# SineGenerator.net
KiCad netlist of a schematic drawn in EAGLE
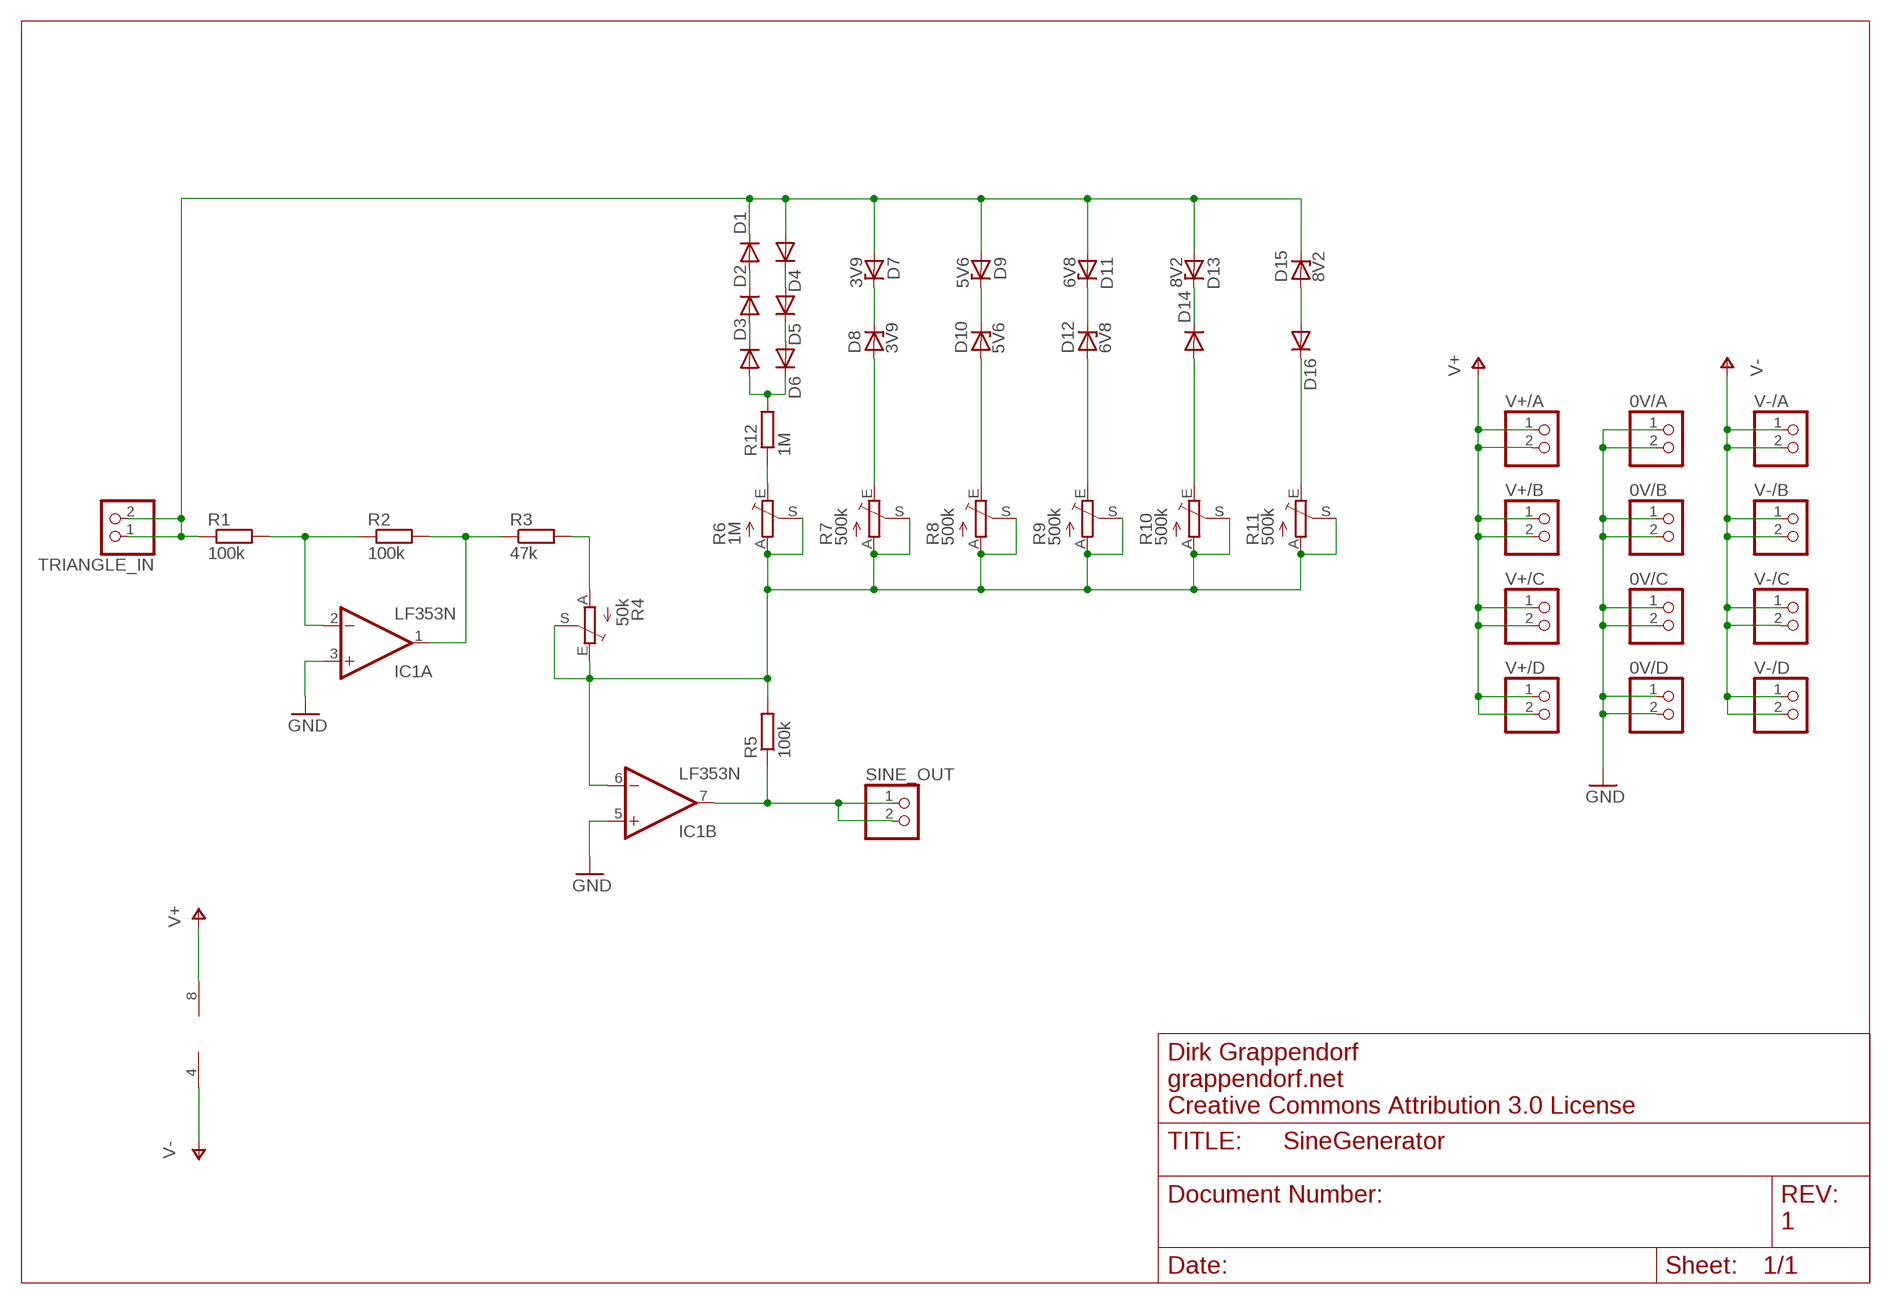
[diagram p0: schematic, sheet 1]

(export (version "E")
  (design (tool "Eeschema 10.0.6"))
  (components
    (comp (ref "0V/A")
      (value "PINHD-1X2")
      (footprint "eagle-import:1X02")
      (libsource (lib "eagle-import") (part "PINHD-1X2"))
    )
    (comp (ref "0V/B")
      (value "PINHD-1X2")
      (footprint "eagle-import:1X02")
      (libsource (lib "eagle-import") (part "PINHD-1X2"))
    )
    (comp (ref "0V/C")
      (value "PINHD-1X2")
      (footprint "eagle-import:1X02")
      (libsource (lib "eagle-import") (part "PINHD-1X2"))
    )
    (comp (ref "0V/D")
      (value "PINHD-1X2")
      (footprint "eagle-import:1X02")
      (libsource (lib "eagle-import") (part "PINHD-1X2"))
    )
    (comp (ref "D1")
      (value "DIODE1N4148")
      (footprint "eagle-import:DIODE-1N4148")
      (libsource (lib "eagle-import") (part "DIODE1N4148"))
    )
    (comp (ref "D2")
      (value "DIODE1N4148")
      (footprint "eagle-import:DIODE-1N4148")
      (libsource (lib "eagle-import") (part "DIODE1N4148"))
    )
    (comp (ref "D3")
      (value "DIODE1N4148")
      (footprint "eagle-import:DIODE-1N4148")
      (libsource (lib "eagle-import") (part "DIODE1N4148"))
    )
    (comp (ref "D4")
      (value "DIODE1N4148")
      (footprint "eagle-import:DIODE-1N4148")
      (libsource (lib "eagle-import") (part "DIODE1N4148"))
    )
    (comp (ref "D5")
      (value "DIODE1N4148")
      (footprint "eagle-import:DIODE-1N4148")
      (libsource (lib "eagle-import") (part "DIODE1N4148"))
    )
    (comp (ref "D6")
      (value "DIODE1N4148")
      (footprint "eagle-import:DIODE-1N4148")
      (libsource (lib "eagle-import") (part "DIODE1N4148"))
    )
    (comp (ref "D7")
      (value "3V9")
      (footprint "eagle-import:DO34Z7")
      (libsource (lib "eagle-import") (part "ZENER-DIODEDO34-7"))
    )
    (comp (ref "D8")
      (value "3V9")
      (footprint "eagle-import:DO34Z7")
      (libsource (lib "eagle-import") (part "ZENER-DIODEDO34-7"))
    )
    (comp (ref "D9")
      (value "5V6")
      (footprint "eagle-import:DO34Z7")
      (libsource (lib "eagle-import") (part "ZENER-DIODEDO34-7"))
    )
    (comp (ref "D10")
      (value "5V6")
      (footprint "eagle-import:DO34Z7")
      (libsource (lib "eagle-import") (part "ZENER-DIODEDO34-7"))
    )
    (comp (ref "D11")
      (value "6V8")
      (footprint "eagle-import:DO34Z7")
      (libsource (lib "eagle-import") (part "ZENER-DIODEDO34-7"))
    )
    (comp (ref "D12")
      (value "6V8")
      (footprint "eagle-import:DO34Z7")
      (libsource (lib "eagle-import") (part "ZENER-DIODEDO34-7"))
    )
    (comp (ref "D13")
      (value "8V2")
      (footprint "eagle-import:DO34Z7")
      (libsource (lib "eagle-import") (part "ZENER-DIODEDO34-7"))
    )
    (comp (ref "D14")
      (value "DIODE1N4148")
      (footprint "eagle-import:DIODE-1N4148")
      (libsource (lib "eagle-import") (part "DIODE1N4148"))
    )
    (comp (ref "D15")
      (value "8V2")
      (footprint "eagle-import:DO34Z7")
      (libsource (lib "eagle-import") (part "ZENER-DIODEDO34-7"))
    )
    (comp (ref "D16")
      (value "DIODE1N4148")
      (footprint "eagle-import:DIODE-1N4148")
      (libsource (lib "eagle-import") (part "DIODE1N4148"))
    )
    (comp (ref "IC1")
      (value "LF353N")
      (footprint "eagle-import:DIL08")
      (libsource (lib "eagle-import") (part "LF353N"))
    )
    (comp (ref "R1")
      (value "100k")
      (footprint "eagle-import:0207_7")
      (libsource (lib "eagle-import") (part "R-EU_0207/7"))
    )
    (comp (ref "R2")
      (value "100k")
      (footprint "eagle-import:0207_7")
      (libsource (lib "eagle-import") (part "R-EU_0207/7"))
    )
    (comp (ref "R3")
      (value "47k")
      (footprint "eagle-import:0207_7")
      (libsource (lib "eagle-import") (part "R-EU_0207/7"))
    )
    (comp (ref "R4")
      (value "50k")
      (footprint "eagle-import:LI15")
      (libsource (lib "eagle-import") (part "TRIM_EU-LI15"))
    )
    (comp (ref "R5")
      (value "100k")
      (footprint "eagle-import:0207_7")
      (libsource (lib "eagle-import") (part "R-EU_0207/7"))
    )
    (comp (ref "R6")
      (value "1M")
      (footprint "eagle-import:ST15")
      (libsource (lib "eagle-import") (part "TRIM_EU-ST15"))
    )
    (comp (ref "R7")
      (value "500k")
      (footprint "eagle-import:ST15")
      (libsource (lib "eagle-import") (part "TRIM_EU-ST15"))
    )
    (comp (ref "R8")
      (value "500k")
      (footprint "eagle-import:ST15")
      (libsource (lib "eagle-import") (part "TRIM_EU-ST15"))
    )
    (comp (ref "R9")
      (value "500k")
      (footprint "eagle-import:ST15")
      (libsource (lib "eagle-import") (part "TRIM_EU-ST15"))
    )
    (comp (ref "R10")
      (value "500k")
      (footprint "eagle-import:ST15")
      (libsource (lib "eagle-import") (part "TRIM_EU-ST15"))
    )
    (comp (ref "R11")
      (value "500k")
      (footprint "eagle-import:ST15")
      (libsource (lib "eagle-import") (part "TRIM_EU-ST15"))
    )
    (comp (ref "R12")
      (value "1M")
      (footprint "eagle-import:0207_7")
      (libsource (lib "eagle-import") (part "R-EU_0207/7"))
    )
    (comp (ref "SINE_OUT")
      (value "PINHD-1X2")
      (footprint "eagle-import:1X02")
      (libsource (lib "eagle-import") (part "PINHD-1X2"))
    )
    (comp (ref "TRIANGLE_IN")
      (value "PINHD-1X2")
      (footprint "eagle-import:1X02")
      (libsource (lib "eagle-import") (part "PINHD-1X2"))
    )
    (comp (ref "V+/A")
      (value "PINHD-1X2")
      (footprint "eagle-import:1X02")
      (libsource (lib "eagle-import") (part "PINHD-1X2"))
    )
    (comp (ref "V+/B")
      (value "PINHD-1X2")
      (footprint "eagle-import:1X02")
      (libsource (lib "eagle-import") (part "PINHD-1X2"))
    )
    (comp (ref "V+/C")
      (value "PINHD-1X2")
      (footprint "eagle-import:1X02")
      (libsource (lib "eagle-import") (part "PINHD-1X2"))
    )
    (comp (ref "V+/D")
      (value "PINHD-1X2")
      (footprint "eagle-import:1X02")
      (libsource (lib "eagle-import") (part "PINHD-1X2"))
    )
    (comp (ref "V-/A")
      (value "PINHD-1X2")
      (footprint "eagle-import:1X02")
      (libsource (lib "eagle-import") (part "PINHD-1X2"))
    )
    (comp (ref "V-/B")
      (value "PINHD-1X2")
      (footprint "eagle-import:1X02")
      (libsource (lib "eagle-import") (part "PINHD-1X2"))
    )
    (comp (ref "V-/C")
      (value "PINHD-1X2")
      (footprint "eagle-import:1X02")
      (libsource (lib "eagle-import") (part "PINHD-1X2"))
    )
    (comp (ref "V-/D")
      (value "PINHD-1X2")
      (footprint "eagle-import:1X02")
      (libsource (lib "eagle-import") (part "PINHD-1X2"))
    )
  )
  (nets
    (net (code "1") (name "GND") (class "Default")
      (node (ref "0V/A") (pin "1") (pinfunction "1_1") (pintype "passive"))
      (node (ref "0V/A") (pin "2") (pinfunction "2_2") (pintype "passive"))
      (node (ref "0V/B") (pin "1") (pinfunction "1_1") (pintype "passive"))
      (node (ref "0V/B") (pin "2") (pinfunction "2_2") (pintype "passive"))
      (node (ref "0V/C") (pin "1") (pinfunction "1_1") (pintype "passive"))
      (node (ref "0V/C") (pin "2") (pinfunction "2_2") (pintype "passive"))
      (node (ref "0V/D") (pin "1") (pinfunction "1_1") (pintype "passive"))
      (node (ref "0V/D") (pin "2") (pinfunction "2_2") (pintype "passive"))
      (node (ref "IC1") (pin "3") (pinfunction "+IN_3") (pintype "input"))
      (node (ref "IC1") (pin "5") (pinfunction "+IN_5") (pintype "input"))
    )
    (net (code "2") (name "Net-(D1-PadA)") (class "Default")
      (node (ref "D1") (pin "A") (pinfunction "A_A") (pintype "passive"))
      (node (ref "D2") (pin "C") (pinfunction "C_C") (pintype "passive"))
    )
    (net (code "3") (name "Net-(D1-PadC)") (class "Default")
      (node (ref "D1") (pin "C") (pinfunction "C_C") (pintype "passive"))
      (node (ref "D11") (pin "A") (pinfunction "A_A") (pintype "passive"))
      (node (ref "D13") (pin "A") (pinfunction "A_A") (pintype "passive"))
      (node (ref "D15") (pin "C") (pinfunction "C_C") (pintype "passive"))
      (node (ref "D4") (pin "A") (pinfunction "A_A") (pintype "passive"))
      (node (ref "D7") (pin "A") (pinfunction "A_A") (pintype "passive"))
      (node (ref "D9") (pin "A") (pinfunction "A_A") (pintype "passive"))
      (node (ref "R1") (pin "1") (pinfunction "1_1") (pintype "passive"))
      (node (ref "TRIANGLE_IN") (pin "1") (pinfunction "1_1") (pintype "passive"))
      (node (ref "TRIANGLE_IN") (pin "2") (pinfunction "2_2") (pintype "passive"))
    )
    (net (code "4") (name "Net-(D2-PadA)") (class "Default")
      (node (ref "D2") (pin "A") (pinfunction "A_A") (pintype "passive"))
      (node (ref "D3") (pin "C") (pinfunction "C_C") (pintype "passive"))
    )
    (net (code "5") (name "Net-(D3-PadA)") (class "Default")
      (node (ref "D3") (pin "A") (pinfunction "A_A") (pintype "passive"))
      (node (ref "D6") (pin "C") (pinfunction "C_C") (pintype "passive"))
      (node (ref "R12") (pin "2") (pinfunction "2_2") (pintype "passive"))
    )
    (net (code "6") (name "Net-(D4-PadC)") (class "Default")
      (node (ref "D4") (pin "C") (pinfunction "C_C") (pintype "passive"))
      (node (ref "D5") (pin "A") (pinfunction "A_A") (pintype "passive"))
    )
    (net (code "7") (name "Net-(D5-PadC)") (class "Default")
      (node (ref "D5") (pin "C") (pinfunction "C_C") (pintype "passive"))
      (node (ref "D6") (pin "A") (pinfunction "A_A") (pintype "passive"))
    )
    (net (code "8") (name "Net-(D7-PadC)") (class "Default")
      (node (ref "D7") (pin "C") (pinfunction "C_C") (pintype "passive"))
      (node (ref "D8") (pin "C") (pinfunction "C_C") (pintype "passive"))
    )
    (net (code "9") (name "Net-(D8-PadA)") (class "Default")
      (node (ref "D8") (pin "A") (pinfunction "A_A") (pintype "passive"))
      (node (ref "R7") (pin "E") (pinfunction "E_E") (pintype "passive"))
    )
    (net (code "10") (name "Net-(D10-PadA)") (class "Default")
      (node (ref "D10") (pin "A") (pinfunction "A_A") (pintype "passive"))
      (node (ref "R8") (pin "E") (pinfunction "E_E") (pintype "passive"))
    )
    (net (code "11") (name "Net-(D10-PadC)") (class "Default")
      (node (ref "D10") (pin "C") (pinfunction "C_C") (pintype "passive"))
      (node (ref "D9") (pin "C") (pinfunction "C_C") (pintype "passive"))
    )
    (net (code "12") (name "Net-(D11-PadC)") (class "Default")
      (node (ref "D11") (pin "C") (pinfunction "C_C") (pintype "passive"))
      (node (ref "D12") (pin "C") (pinfunction "C_C") (pintype "passive"))
    )
    (net (code "13") (name "Net-(D12-PadA)") (class "Default")
      (node (ref "D12") (pin "A") (pinfunction "A_A") (pintype "passive"))
      (node (ref "R9") (pin "E") (pinfunction "E_E") (pintype "passive"))
    )
    (net (code "14") (name "Net-(D13-PadC)") (class "Default")
      (node (ref "D13") (pin "C") (pinfunction "C_C") (pintype "passive"))
      (node (ref "D14") (pin "C") (pinfunction "C_C") (pintype "passive"))
    )
    (net (code "15") (name "Net-(D14-PadA)") (class "Default")
      (node (ref "D14") (pin "A") (pinfunction "A_A") (pintype "passive"))
      (node (ref "R10") (pin "E") (pinfunction "E_E") (pintype "passive"))
    )
    (net (code "16") (name "Net-(D15-PadA)") (class "Default")
      (node (ref "D15") (pin "A") (pinfunction "A_A") (pintype "passive"))
      (node (ref "D16") (pin "A") (pinfunction "A_A") (pintype "passive"))
    )
    (net (code "17") (name "Net-(D16-PadC)") (class "Default")
      (node (ref "D16") (pin "C") (pinfunction "C_C") (pintype "passive"))
      (node (ref "R11") (pin "E") (pinfunction "E_E") (pintype "passive"))
    )
    (net (code "18") (name "Net-(IC1A--IN)") (class "Default")
      (node (ref "IC1") (pin "2") (pinfunction "-IN_2") (pintype "input"))
      (node (ref "R1") (pin "2") (pinfunction "2_2") (pintype "passive"))
      (node (ref "R2") (pin "1") (pinfunction "1_1") (pintype "passive"))
    )
    (net (code "19") (name "Net-(IC1A-OUT)") (class "Default")
      (node (ref "IC1") (pin "1") (pinfunction "OUT_1") (pintype "output"))
      (node (ref "R2") (pin "2") (pinfunction "2_2") (pintype "passive"))
      (node (ref "R3") (pin "1") (pinfunction "1_1") (pintype "passive"))
    )
    (net (code "20") (name "Net-(IC1B--IN)") (class "Default")
      (node (ref "IC1") (pin "6") (pinfunction "-IN_6") (pintype "input"))
      (node (ref "R10") (pin "A") (pinfunction "A_A") (pintype "passive"))
      (node (ref "R10") (pin "S") (pinfunction "S_S") (pintype "passive"))
      (node (ref "R11") (pin "A") (pinfunction "A_A") (pintype "passive"))
      (node (ref "R11") (pin "S") (pinfunction "S_S") (pintype "passive"))
      (node (ref "R4") (pin "E") (pinfunction "E_E") (pintype "passive"))
      (node (ref "R4") (pin "S") (pinfunction "S_S") (pintype "passive"))
      (node (ref "R5") (pin "2") (pinfunction "2_2") (pintype "passive"))
      (node (ref "R6") (pin "A") (pinfunction "A_A") (pintype "passive"))
      (node (ref "R6") (pin "S") (pinfunction "S_S") (pintype "passive"))
      (node (ref "R7") (pin "A") (pinfunction "A_A") (pintype "passive"))
      (node (ref "R7") (pin "S") (pinfunction "S_S") (pintype "passive"))
      (node (ref "R8") (pin "A") (pinfunction "A_A") (pintype "passive"))
      (node (ref "R8") (pin "S") (pinfunction "S_S") (pintype "passive"))
      (node (ref "R9") (pin "A") (pinfunction "A_A") (pintype "passive"))
      (node (ref "R9") (pin "S") (pinfunction "S_S") (pintype "passive"))
    )
    (net (code "21") (name "Net-(IC1B-OUT)") (class "Default")
      (node (ref "IC1") (pin "7") (pinfunction "OUT_7") (pintype "output"))
      (node (ref "R5") (pin "1") (pinfunction "1_1") (pintype "passive"))
      (node (ref "SINE_OUT") (pin "1") (pinfunction "1_1") (pintype "passive"))
      (node (ref "SINE_OUT") (pin "2") (pinfunction "2_2") (pintype "passive"))
    )
    (net (code "22") (name "Net-(R3-Pad2)") (class "Default")
      (node (ref "R3") (pin "2") (pinfunction "2_2") (pintype "passive"))
      (node (ref "R4") (pin "A") (pinfunction "A_A") (pintype "passive"))
    )
    (net (code "23") (name "Net-(R12-Pad1)") (class "Default")
      (node (ref "R12") (pin "1") (pinfunction "1_1") (pintype "passive"))
      (node (ref "R6") (pin "E") (pinfunction "E_E") (pintype "passive"))
    )
    (net (code "24") (name "V+") (class "Default")
      (node (ref "IC1") (pin "8") (pinfunction "V+_8") (pintype "power_in"))
      (node (ref "V+/A") (pin "1") (pinfunction "1_1") (pintype "passive"))
      (node (ref "V+/A") (pin "2") (pinfunction "2_2") (pintype "passive"))
      (node (ref "V+/B") (pin "1") (pinfunction "1_1") (pintype "passive"))
      (node (ref "V+/B") (pin "2") (pinfunction "2_2") (pintype "passive"))
      (node (ref "V+/C") (pin "1") (pinfunction "1_1") (pintype "passive"))
      (node (ref "V+/C") (pin "2") (pinfunction "2_2") (pintype "passive"))
      (node (ref "V+/D") (pin "1") (pinfunction "1_1") (pintype "passive"))
      (node (ref "V+/D") (pin "2") (pinfunction "2_2") (pintype "passive"))
    )
    (net (code "25") (name "V-") (class "Default")
      (node (ref "IC1") (pin "4") (pinfunction "V-_4") (pintype "power_in"))
      (node (ref "V-/A") (pin "1") (pinfunction "1_1") (pintype "passive"))
      (node (ref "V-/A") (pin "2") (pinfunction "2_2") (pintype "passive"))
      (node (ref "V-/B") (pin "1") (pinfunction "1_1") (pintype "passive"))
      (node (ref "V-/B") (pin "2") (pinfunction "2_2") (pintype "passive"))
      (node (ref "V-/C") (pin "1") (pinfunction "1_1") (pintype "passive"))
      (node (ref "V-/C") (pin "2") (pinfunction "2_2") (pintype "passive"))
      (node (ref "V-/D") (pin "1") (pinfunction "1_1") (pintype "passive"))
      (node (ref "V-/D") (pin "2") (pinfunction "2_2") (pintype "passive"))
    )
  )
)
